# Sheet1.net
KiCad netlist of a schematic drawn in Altium Designer
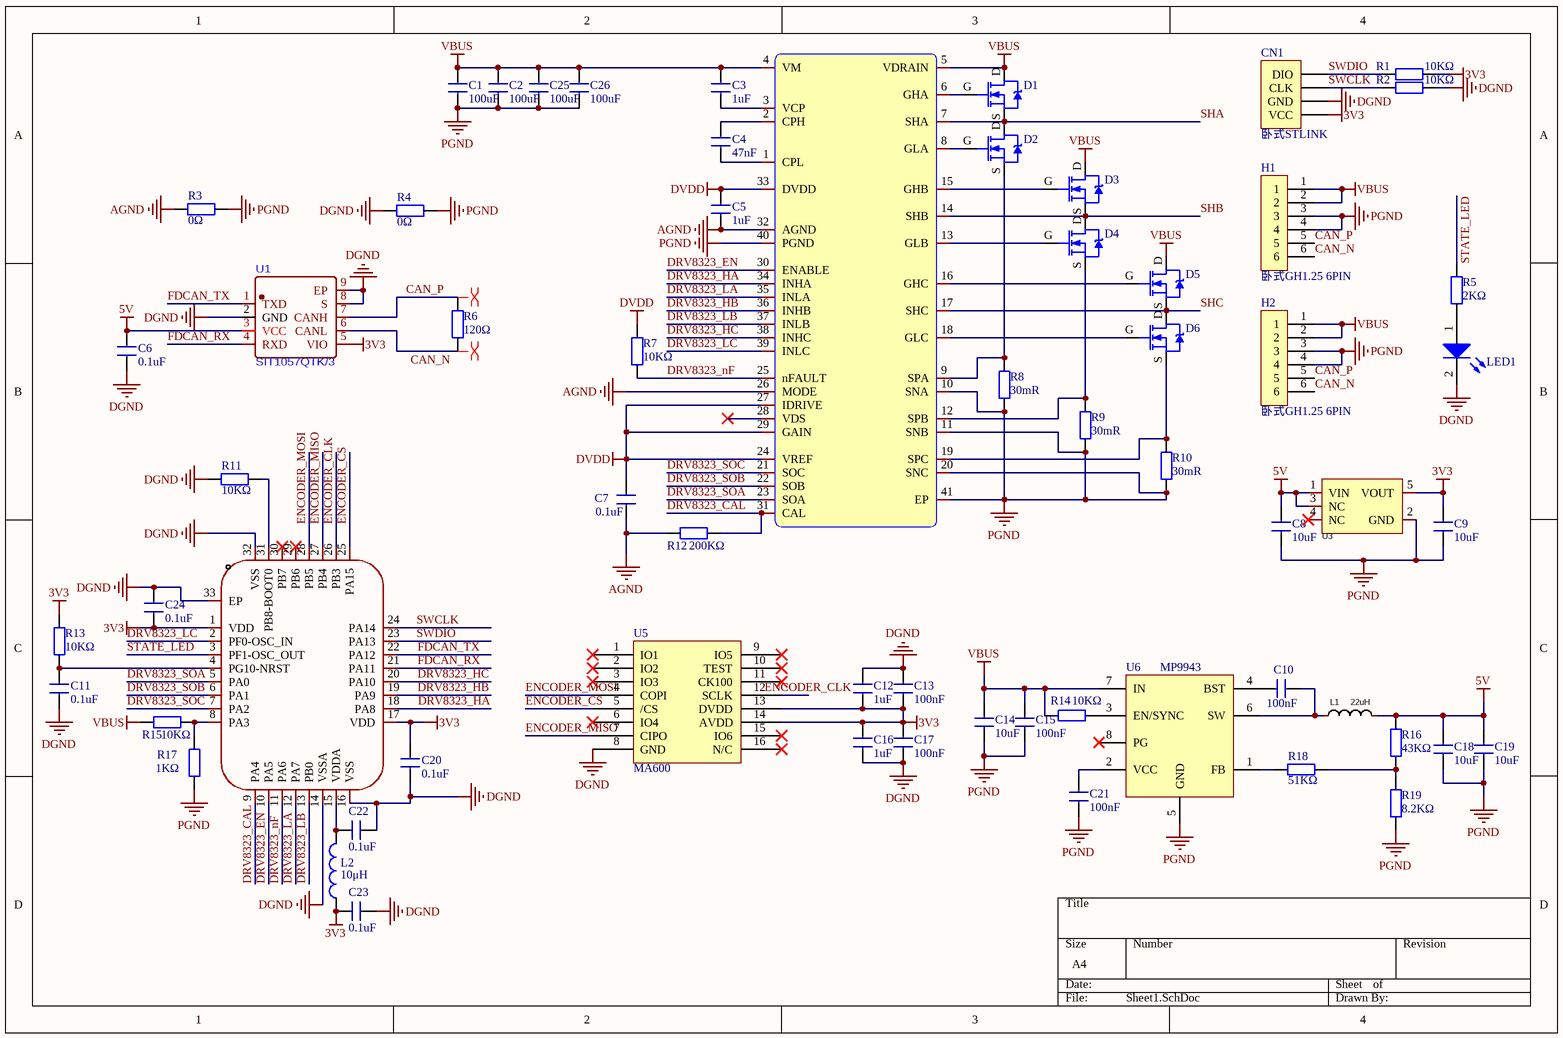
[diagram p0: Sheet1.SchDoc]

(export (version "E")
  (design (tool "Eeschema 10.0.6"))
  (components
    (comp (ref "C1")
      (value "100uF")
      (footprint "1206")
      (description "1210贴片电容")
      (libsource (lib "Integrated_Library1") (part "1210贴片电容"))
    )
    (comp (ref "C2")
      (value "100uF")
      (footprint "1206")
      (description "1210贴片电容")
      (libsource (lib "Integrated_Library1") (part "1210贴片电容"))
    )
    (comp (ref "C3")
      (value "1uF")
      (footprint "c0402")
      (description "贴片电容0402")
      (libsource (lib "Integrated_Library1") (part "0402贴片电容"))
    )
    (comp (ref "C4")
      (value "47nF")
      (footprint "c0402")
      (description "贴片电容0402")
      (libsource (lib "Integrated_Library1") (part "0402贴片电容"))
    )
    (comp (ref "C5")
      (value "1uF")
      (footprint "c0402")
      (description "贴片电容0402")
      (libsource (lib "Integrated_Library1") (part "0402贴片电容"))
    )
    (comp (ref "C6")
      (value "0.1uF")
      (footprint "c0402")
      (description "贴片电容0402")
      (libsource (lib "Integrated_Library1") (part "0402贴片电容"))
    )
    (comp (ref "C7")
      (value "0.1uF")
      (footprint "c0402")
      (description "贴片电容0402")
      (libsource (lib "Integrated_Library1") (part "0402贴片电容"))
    )
    (comp (ref "C8")
      (value "10uF")
      (footprint "c0402")
      (description "贴片电容0402")
      (libsource (lib "Integrated_Library1") (part "0402贴片电容"))
    )
    (comp (ref "C9")
      (value "10uF")
      (footprint "c0402")
      (description "贴片电容0402")
      (libsource (lib "Integrated_Library1") (part "0402贴片电容"))
    )
    (comp (ref "C10")
      (value "100nF")
      (footprint "c0402")
      (description "贴片电容0402")
      (libsource (lib "Integrated_Library1") (part "0402贴片电容"))
    )
    (comp (ref "C11")
      (value "0.1uF")
      (footprint "c0402")
      (description "贴片电容0402")
      (libsource (lib "Integrated_Library1") (part "0402贴片电容"))
    )
    (comp (ref "C12")
      (value "1uF")
      (footprint "C0402")
      (description "贴片电容0402")
      (libsource (lib "Integrated_Library1") (part "0402贴片电容"))
    )
    (comp (ref "C13")
      (value "100nF")
      (footprint "C0402")
      (description "贴片电容0402")
      (libsource (lib "Integrated_Library1") (part "0402贴片电容"))
    )
    (comp (ref "C14")
      (value "10uF")
      (footprint "C0603")
      (description "1210贴片电容")
      (libsource (lib "Integrated_Library1") (part "1210贴片电容"))
    )
    (comp (ref "C15")
      (value "100nF")
      (footprint "c0402")
      (description "贴片电容0402")
      (libsource (lib "Integrated_Library1") (part "0402贴片电容"))
    )
    (comp (ref "C16")
      (value "1uF")
      (footprint "C0402")
      (description "贴片电容0402")
      (libsource (lib "Integrated_Library1") (part "0402贴片电容"))
    )
    (comp (ref "C17")
      (value "100nF")
      (footprint "C0402")
      (description "贴片电容0402")
      (libsource (lib "Integrated_Library1") (part "0402贴片电容"))
    )
    (comp (ref "C18")
      (value "10uF")
      (footprint "C0603")
      (description "1210贴片电容")
      (libsource (lib "Integrated_Library1") (part "1210贴片电容"))
    )
    (comp (ref "C19")
      (value "10uF")
      (footprint "C0603")
      (description "1210贴片电容")
      (libsource (lib "Integrated_Library1") (part "1210贴片电容"))
    )
    (comp (ref "C20")
      (value "0.1uF")
      (footprint "c0402")
      (description "贴片电容0402")
      (libsource (lib "Integrated_Library1") (part "0402贴片电容"))
    )
    (comp (ref "C21")
      (value "100nF")
      (footprint "c0402")
      (description "贴片电容0402")
      (libsource (lib "Integrated_Library1") (part "0402贴片电容"))
    )
    (comp (ref "C22")
      (value "0.1uF")
      (footprint "c0402")
      (description "贴片电容0402")
      (libsource (lib "Integrated_Library1") (part "0402贴片电容"))
    )
    (comp (ref "C23")
      (value "0.1uF")
      (footprint "c0402")
      (description "贴片电容0402")
      (libsource (lib "Integrated_Library1") (part "0402贴片电容"))
    )
    (comp (ref "C24")
      (value "0.1uF")
      (footprint "c0402")
      (description "贴片电容0402")
      (libsource (lib "Integrated_Library1") (part "0402贴片电容"))
    )
    (comp (ref "C25")
      (value "100uF")
      (footprint "1206")
      (description "1210贴片电容")
      (libsource (lib "Integrated_Library1") (part "1210贴片电容"))
    )
    (comp (ref "C26")
      (value "100uF")
      (footprint "1206")
      (description "1210贴片电容")
      (libsource (lib "Integrated_Library1") (part "1210贴片电容"))
    )
    (comp (ref "CN1")
      (value "卧式STLINK")
      (footprint "CONN-SMD_4P-P1.25_GH1.25-4P")
      (libsource (lib "Integrated_Library1") (part "卧式STLINK"))
    )
    (comp (ref "D1")
      (value "NTMFS5C410NL")
      (footprint "DFN-8_L3.0-W3.0-P0.65-BL")
      (description "N沟道MOS管")
      (fields (field (name "PUBLISHER") "Altium Limited"))
      (libsource (lib "En") (part "NTMFS5C410NL"))
    )
    (comp (ref "D2")
      (value "NTMFS5C410NL")
      (footprint "DFN-8_L3.0-W3.0-P0.65-BL")
      (description "N沟道MOS管")
      (fields (field (name "PUBLISHER") "Altium Limited"))
      (libsource (lib "En") (part "NTMFS5C410NL"))
    )
    (comp (ref "D3")
      (value "NTMFS5C410NL")
      (footprint "DFN-8_L3.0-W3.0-P0.65-BL")
      (description "N沟道MOS管")
      (fields (field (name "PUBLISHER") "Altium Limited"))
      (libsource (lib "En") (part "NTMFS5C410NL"))
    )
    (comp (ref "D4")
      (value "NTMFS5C410NL")
      (footprint "DFN-8_L3.0-W3.0-P0.65-BL")
      (description "N沟道MOS管")
      (fields (field (name "PUBLISHER") "Altium Limited"))
      (libsource (lib "En") (part "NTMFS5C410NL"))
    )
    (comp (ref "D5")
      (value "NTMFS5C410NL")
      (footprint "DFN-8_L3.0-W3.0-P0.65-BL")
      (description "N沟道MOS管")
      (fields (field (name "PUBLISHER") "Altium Limited"))
      (libsource (lib "En") (part "NTMFS5C410NL"))
    )
    (comp (ref "D6")
      (value "NTMFS5C410NL")
      (footprint "DFN-8_L3.0-W3.0-P0.65-BL")
      (description "N沟道MOS管")
      (fields (field (name "PUBLISHER") "Altium Limited"))
      (libsource (lib "En") (part "NTMFS5C410NL"))
    )
    (comp (ref "H1")
      (value "卧式GH1.25 6PIN")
      (footprint "CONN-SMD_6P-P1.50_ZX-ZH1.5-6PWT")
      (libsource (lib "Integrated_Library1") (part "卧式GH1.25 6PIN"))
    )
    (comp (ref "H2")
      (value "卧式GH1.25 6PIN")
      (footprint "CONN-SMD_6P-P1.50_ZX-ZH1.5-6PWT")
      (libsource (lib "Integrated_Library1") (part "卧式GH1.25 6PIN"))
    )
    (comp (ref "L1")
      (value "22uH")
      (footprint "IND-SMD_L2.5-W2.0")
      (description "一体成型屏蔽电感，0530封装，额定电流3A")
      (fields (field (name "MANUFACTURER") "XR(祥如)") (field (name "MANUFACTURER PART") "XR0530-100M"))
      (libsource (lib "Integrated_Library1") (part "0530屏蔽电感"))
    )
    (comp (ref "L2")
      (value "10μH")
      (footprint "L0805")
      (description "0805贴片电感")
      (libsource (lib "Integrated_Library1") (part "0805贴片电感"))
    )
    (comp (ref "LED1")
      (value "LED")
      (footprint "led0805")
      (description "0805贴片LED")
      (libsource (lib "Integrated_Library1") (part "0805贴片LED"))
    )
    (comp (ref "R1")
      (value "10KΩ")
      (footprint "R0402")
      (description "0402贴片电阻")
      (libsource (lib "") (part "0402贴片电阻_3"))
    )
    (comp (ref "R2")
      (value "10KΩ")
      (footprint "R0402")
      (description "0402贴片电阻")
      (libsource (lib "") (part "0402贴片电阻_3"))
    )
    (comp (ref "R3")
      (value "0Ω")
      (footprint "R0402")
      (description "0402贴片电阻")
      (libsource (lib "") (part "0402贴片电阻_3"))
    )
    (comp (ref "R4")
      (value "0Ω")
      (footprint "R0402")
      (description "0402贴片电阻")
      (libsource (lib "") (part "0402贴片电阻_3"))
    )
    (comp (ref "R5")
      (value "2KΩ")
      (footprint "R0402")
      (description "0402贴片电阻")
      (libsource (lib "Integrated_Library1") (part "0402贴片电阻"))
    )
    (comp (ref "R6")
      (value "120Ω")
      (footprint "R0402")
      (description "0402贴片电阻")
      (libsource (lib "") (part "0402贴片电阻_5"))
    )
    (comp (ref "R7")
      (value "10KΩ")
      (footprint "R0402")
      (description "0402贴片电阻")
      (libsource (lib "Integrated_Library1") (part "0402贴片电阻"))
    )
    (comp (ref "R8")
      (value "30mR")
      (footprint "1206")
      (description "2512检流电阻")
      (libsource (lib "Integrated_Library1") (part "2512检流电阻"))
    )
    (comp (ref "R9")
      (value "30mR")
      (footprint "1206")
      (description "2512检流电阻")
      (libsource (lib "Integrated_Library1") (part "2512检流电阻"))
    )
    (comp (ref "R10")
      (value "30mR")
      (footprint "1206")
      (description "2512检流电阻")
      (libsource (lib "Integrated_Library1") (part "2512检流电阻"))
    )
    (comp (ref "R11")
      (value "10KΩ")
      (footprint "R0402")
      (description "0402贴片电阻")
      (libsource (lib "") (part "0402贴片电阻_3"))
    )
    (comp (ref "R12")
      (value "200KΩ")
      (footprint "R0402")
      (description "0402贴片电阻")
      (libsource (lib "") (part "0402贴片电阻_2"))
    )
    (comp (ref "R13")
      (value "10KΩ")
      (footprint "R0402")
      (description "0402贴片电阻")
      (libsource (lib "Integrated_Library1") (part "0402贴片电阻"))
    )
    (comp (ref "R14")
      (value "10KΩ")
      (footprint "R0402")
      (description "0402贴片电阻")
      (libsource (lib "") (part "0402贴片电阻_1"))
    )
    (comp (ref "R15")
      (value "10KΩ")
      (footprint "R0402")
      (description "0402贴片电阻")
      (libsource (lib "") (part "0402贴片电阻_2"))
    )
    (comp (ref "R16")
      (value "43KΩ")
      (footprint "R0402")
      (description "0402贴片电阻")
      (libsource (lib "") (part "0402贴片电阻_4"))
    )
    (comp (ref "R17")
      (value "1KΩ")
      (footprint "R0402")
      (description "0402贴片电阻")
      (libsource (lib "Integrated_Library1") (part "0402贴片电阻"))
    )
    (comp (ref "R18")
      (value "51KΩ")
      (footprint "R0402")
      (description "0402贴片电阻")
      (libsource (lib "") (part "0402贴片电阻_1"))
    )
    (comp (ref "R19")
      (value "8.2KΩ")
      (footprint "R0402")
      (description "0402贴片电阻")
      (libsource (lib "") (part "0402贴片电阻_4"))
    )
    (comp (ref "U1")
      (value "SIT1057QTK/3")
      (footprint "DFN-8_L3.0-W3.0-P0.65-BL-EP")
      (libsource (lib "En") (part "SIT1057QTK/3"))
    )
    (comp (ref "U2")
      (value "DRV8323HRTAR")
      (footprint "QFN-40_L6.0-W6.0-P0.50-BL-EP4.5")
      (fields (field (name "MANUFACTURER") "TI(德州仪器)"))
      (libsource (lib "Integrated_Library1") (part "DRV8323HRTAR"))
    )
    (comp (ref "U3")
      (value "XC6201P332MR-HXY")
      (footprint "SOT-23-5_L3.0-W1.7-P0.95-LS2.8-BR")
      (description "3.3V LDO")
      (fields (field (name "MANUFACTURER") "HXY MOSFET(华轩阳电子)"))
      (libsource (lib "Integrated_Library1") (part "XC6201P332MR-HXY"))
    )
    (comp (ref "U4")
      (value "STM32G431KBU3")
      (footprint "UFQFPN-32_L5.0-W5.0-P0.50-BL-EP3.5")
      (fields (field (name "MANUFACTURER") "ST(意法半导体)"))
      (libsource (lib "Integrated_Library1") (part "STM32G431KBU3"))
    )
    (comp (ref "U5")
      (value "MA600")
      (footprint "qfn-16-l3.0-w3.0-p0.50-tl-ep1.7")
      (description "磁编码器")
      (libsource (lib "Integrated_Library1") (part "MA600"))
    )
    (comp (ref "U6")
      (value "MP9943")
      (footprint "QFN-8 3x3")
      (libsource (lib "Integrated_Library1") (part "MP9943"))
    )
  )
  (nets
    (net (code "2") (name "/CAN_N") (class "Default")
      (node (ref "H1") (pin "6") (pinfunction "6_6") (pintype "passive"))
      (node (ref "H2") (pin "6") (pinfunction "6_6") (pintype "passive"))
      (node (ref "R6") (pin "1") (pinfunction "1_1") (pintype "passive"))
      (node (ref "U1") (pin "6") (pinfunction "CANL_6") (pintype "passive"))
    )
    (net (code "3") (name "/CAN_P") (class "Default")
      (node (ref "H1") (pin "5") (pinfunction "5_5") (pintype "passive"))
      (node (ref "H2") (pin "5") (pinfunction "5_5") (pintype "passive"))
      (node (ref "R6") (pin "2") (pinfunction "2_2") (pintype "passive"))
      (node (ref "U1") (pin "7") (pinfunction "CANH_7") (pintype "passive"))
    )
    (net (code "4") (name "/DRV8323_CAL") (class "Default")
      (node (ref "R12") (pin "1") (pinfunction "1_1") (pintype "passive"))
      (node (ref "U2") (pin "31") (pinfunction "CAL_31") (pintype "passive"))
      (node (ref "U4") (pin "9") (pinfunction "PA4_9") (pintype "passive"))
    )
    (net (code "5") (name "/DRV8323_EN") (class "Default")
      (node (ref "U2") (pin "30") (pinfunction "ENABLE_30") (pintype "passive"))
      (node (ref "U4") (pin "10") (pinfunction "PA5_10") (pintype "passive"))
    )
    (net (code "6") (name "/DRV8323_HA") (class "Default")
      (node (ref "U2") (pin "34") (pinfunction "INHA_34") (pintype "passive"))
      (node (ref "U4") (pin "18") (pinfunction "PA8_18") (pintype "passive"))
    )
    (net (code "7") (name "/DRV8323_HB") (class "Default")
      (node (ref "U2") (pin "36") (pinfunction "INHB_36") (pintype "passive"))
      (node (ref "U4") (pin "19") (pinfunction "PA9_19") (pintype "passive"))
    )
    (net (code "8") (name "/DRV8323_HC") (class "Default")
      (node (ref "U2") (pin "38") (pinfunction "INHC_38") (pintype "passive"))
      (node (ref "U4") (pin "20") (pinfunction "PA10_20") (pintype "passive"))
    )
    (net (code "9") (name "/DRV8323_LA") (class "Default")
      (node (ref "U2") (pin "35") (pinfunction "INLA_35") (pintype "passive"))
      (node (ref "U4") (pin "12") (pinfunction "PA7_12") (pintype "passive"))
    )
    (net (code "10") (name "/DRV8323_LB") (class "Default")
      (node (ref "U2") (pin "37") (pinfunction "INLB_37") (pintype "passive"))
      (node (ref "U4") (pin "13") (pinfunction "PB0_13") (pintype "passive"))
    )
    (net (code "11") (name "/DRV8323_LC") (class "Default")
      (node (ref "U2") (pin "39") (pinfunction "INLC_39") (pintype "passive"))
      (node (ref "U4") (pin "2") (pinfunction "PF0-OSC_IN_2") (pintype "passive"))
    )
    (net (code "12") (name "/DRV8323_SOA") (class "Default")
      (node (ref "U2") (pin "23") (pinfunction "SOA_23") (pintype "passive"))
      (node (ref "U4") (pin "5") (pinfunction "PA0_5") (pintype "passive"))
    )
    (net (code "13") (name "/DRV8323_SOB") (class "Default")
      (node (ref "U2") (pin "22") (pinfunction "SOB_22") (pintype "passive"))
      (node (ref "U4") (pin "6") (pinfunction "PA1_6") (pintype "passive"))
    )
    (net (code "14") (name "/DRV8323_SOC") (class "Default")
      (node (ref "U2") (pin "21") (pinfunction "SOC_21") (pintype "passive"))
      (node (ref "U4") (pin "7") (pinfunction "PA2_7") (pintype "passive"))
    )
    (net (code "15") (name "/DRV8323_nF") (class "Default")
      (node (ref "R7") (pin "2") (pinfunction "2_2") (pintype "passive"))
      (node (ref "U2") (pin "25") (pinfunction "nFAULT_25") (pintype "passive"))
      (node (ref "U4") (pin "11") (pinfunction "PA6_11") (pintype "passive"))
    )
    (net (code "16") (name "/ENCODER_CLK") (class "Default")
      (node (ref "U4") (pin "26") (pinfunction "PB3_26") (pintype "passive"))
      (node (ref "U5") (pin "12") (pinfunction "SCLK_12") (pintype "passive"))
    )
    (net (code "17") (name "/ENCODER_CS") (class "Default")
      (node (ref "U4") (pin "25") (pinfunction "PA15_25") (pintype "passive"))
      (node (ref "U5") (pin "5") (pinfunction "/CS_5") (pintype "passive"))
    )
    (net (code "18") (name "/ENCODER_MISO") (class "Default")
      (node (ref "U4") (pin "27") (pinfunction "PB4_27") (pintype "passive"))
      (node (ref "U5") (pin "7") (pinfunction "CIPO_7") (pintype "passive"))
    )
    (net (code "19") (name "/ENCODER_MOSI") (class "Default")
      (node (ref "U4") (pin "28") (pinfunction "PB5_28") (pintype "passive"))
      (node (ref "U5") (pin "4") (pinfunction "COPI_4") (pintype "passive"))
    )
    (net (code "20") (name "/FDCAN_RX") (class "Default")
      (node (ref "U1") (pin "4") (pinfunction "RXD_4") (pintype "passive"))
      (node (ref "U4") (pin "21") (pinfunction "PA11_21") (pintype "passive"))
    )
    (net (code "21") (name "/FDCAN_TX") (class "Default")
      (node (ref "U1") (pin "1") (pinfunction "TXD_1") (pintype "passive"))
      (node (ref "U4") (pin "22") (pinfunction "PA12_22") (pintype "passive"))
    )
    (net (code "22") (name "/SHA") (class "Default")
      (node (ref "D1") (pin "S") (pinfunction "S_S") (pintype "passive"))
      (node (ref "D2") (pin "D") (pinfunction "D_D") (pintype "passive"))
      (node (ref "U2") (pin "7") (pinfunction "SHA_7") (pintype "passive"))
    )
    (net (code "23") (name "/SHB") (class "Default")
      (node (ref "D3") (pin "S") (pinfunction "S_S") (pintype "passive"))
      (node (ref "D4") (pin "D") (pinfunction "D_D") (pintype "passive"))
      (node (ref "U2") (pin "14") (pinfunction "SHB_14") (pintype "passive"))
    )
    (net (code "24") (name "/SHC") (class "Default")
      (node (ref "D5") (pin "S") (pinfunction "S_S") (pintype "passive"))
      (node (ref "D6") (pin "D") (pinfunction "D_D") (pintype "passive"))
      (node (ref "U2") (pin "17") (pinfunction "SHC_17") (pintype "passive"))
    )
    (net (code "25") (name "/STATE_LED") (class "Default")
      (node (ref "R5") (pin "1") (pinfunction "1_1") (pintype "passive"))
      (node (ref "U4") (pin "3") (pinfunction "PF1-OSC_OUT_3") (pintype "passive"))
    )
    (net (code "26") (name "/SWCLK") (class "Default")
      (node (ref "CN1") (pin "3") (pinfunction "CLK_3") (pintype "passive"))
      (node (ref "R2") (pin "1") (pinfunction "1_1") (pintype "passive"))
      (node (ref "U4") (pin "24") (pinfunction "PA14_24") (pintype "passive"))
    )
    (net (code "27") (name "/SWDIO") (class "Default")
      (node (ref "CN1") (pin "4") (pinfunction "DIO_4") (pintype "passive"))
      (node (ref "R1") (pin "1") (pinfunction "1_1") (pintype "passive"))
      (node (ref "U4") (pin "23") (pinfunction "PA13_23") (pintype "passive"))
    )
    (net (code "28") (name "3V3") (class "Default")
      (node (ref "C12") (pin "1") (pinfunction "1_1") (pintype "passive"))
      (node (ref "C13") (pin "1") (pinfunction "1_1") (pintype "passive"))
      (node (ref "C16") (pin "2") (pinfunction "2_2") (pintype "passive"))
      (node (ref "C17") (pin "2") (pinfunction "2_2") (pintype "passive"))
      (node (ref "C20") (pin "1") (pinfunction "1_1") (pintype "passive"))
      (node (ref "C23") (pin "2") (pinfunction "2_2") (pintype "passive"))
      (node (ref "C24") (pin "1") (pinfunction "1_1") (pintype "passive"))
      (node (ref "C9") (pin "2") (pinfunction "2_2") (pintype "passive"))
      (node (ref "CN1") (pin "1") (pinfunction "VCC_1") (pintype "passive"))
      (node (ref "L2") (pin "1") (pinfunction "1_1") (pintype "passive"))
      (node (ref "R1") (pin "2") (pinfunction "2_2") (pintype "passive"))
      (node (ref "R13") (pin "1") (pinfunction "1_1") (pintype "passive"))
      (node (ref "U1") (pin "5") (pinfunction "VIO_5") (pintype "passive"))
      (node (ref "U3") (pin "5") (pinfunction "VOUT_5") (pintype "passive"))
      (node (ref "U4") (pin "1") (pinfunction "VDD_1") (pintype "passive"))
      (node (ref "U4") (pin "17") (pinfunction "VDD_17") (pintype "passive"))
      (node (ref "U5") (pin "13") (pinfunction "DVDD_13") (pintype "passive"))
      (node (ref "U5") (pin "14") (pinfunction "AVDD_14") (pintype "passive"))
    )
    (net (code "29") (name "5V") (class "Default")
      (node (ref "C18") (pin "2") (pinfunction "2_2") (pintype "passive"))
      (node (ref "C19") (pin "2") (pinfunction "2_2") (pintype "passive"))
      (node (ref "C6") (pin "2") (pinfunction "2_2") (pintype "passive"))
      (node (ref "C8") (pin "2") (pinfunction "2_2") (pintype "passive"))
      (node (ref "L1") (pin "2") (pinfunction "2_2") (pintype "passive"))
      (node (ref "R16") (pin "2") (pinfunction "2_2") (pintype "passive"))
      (node (ref "U1") (pin "3") (pinfunction "VCC_3") (pintype "passive"))
      (node (ref "U3") (pin "1") (pinfunction "VIN_1") (pintype "passive"))
      (node (ref "U3") (pin "3") (pinfunction "NC_3") (pintype "passive"))
    )
    (net (code "30") (name "AGND") (class "Default")
      (node (ref "C5") (pin "1") (pinfunction "1_1") (pintype "passive"))
      (node (ref "C7") (pin "1") (pinfunction "1_1") (pintype "passive"))
      (node (ref "R12") (pin "2") (pinfunction "2_2") (pintype "passive"))
      (node (ref "R3") (pin "1") (pinfunction "1_1") (pintype "passive"))
      (node (ref "U2") (pin "26") (pinfunction "MODE_26") (pintype "passive"))
      (node (ref "U2") (pin "32") (pinfunction "AGND_32") (pintype "passive"))
    )
    (net (code "31") (name "DGND") (class "Default")
      (node (ref "C11") (pin "1") (pinfunction "1_1") (pintype "passive"))
      (node (ref "C12") (pin "2") (pinfunction "2_2") (pintype "passive"))
      (node (ref "C13") (pin "2") (pinfunction "2_2") (pintype "passive"))
      (node (ref "C16") (pin "1") (pinfunction "1_1") (pintype "passive"))
      (node (ref "C17") (pin "1") (pinfunction "1_1") (pintype "passive"))
      (node (ref "C20") (pin "2") (pinfunction "2_2") (pintype "passive"))
      (node (ref "C22") (pin "1") (pinfunction "1_1") (pintype "passive"))
      (node (ref "C23") (pin "1") (pinfunction "1_1") (pintype "passive"))
      (node (ref "C24") (pin "2") (pinfunction "2_2") (pintype "passive"))
      (node (ref "C6") (pin "1") (pinfunction "1_1") (pintype "passive"))
      (node (ref "CN1") (pin "2") (pinfunction "GND_2") (pintype "passive"))
      (node (ref "LED1") (pin "2") (pinfunction "K_2") (pintype "passive"))
      (node (ref "R11") (pin "1") (pinfunction "1_1") (pintype "passive"))
      (node (ref "R2") (pin "2") (pinfunction "2_2") (pintype "passive"))
      (node (ref "R4") (pin "1") (pinfunction "1_1") (pintype "passive"))
      (node (ref "U1") (pin "2") (pinfunction "GND_2") (pintype "passive"))
      (node (ref "U1") (pin "8") (pinfunction "S_8") (pintype "passive"))
      (node (ref "U1") (pin "9") (pinfunction "EP_9") (pintype "passive"))
      (node (ref "U4") (pin "14") (pinfunction "VSSA_14") (pintype "passive"))
      (node (ref "U4") (pin "16") (pinfunction "VSS_16") (pintype "passive"))
      (node (ref "U4") (pin "32") (pinfunction "VSS_32") (pintype "passive"))
      (node (ref "U4") (pin "33") (pinfunction "EP_33") (pintype "passive"))
      (node (ref "U5") (pin "8") (pinfunction "GND_8") (pintype "passive"))
    )
    (net (code "32") (name "DVDD") (class "Default")
      (node (ref "C5") (pin "2") (pinfunction "2_2") (pintype "passive"))
      (node (ref "C7") (pin "2") (pinfunction "2_2") (pintype "passive"))
      (node (ref "R7") (pin "1") (pinfunction "1_1") (pintype "passive"))
      (node (ref "U2") (pin "24") (pinfunction "VREF_24") (pintype "passive"))
      (node (ref "U2") (pin "27") (pinfunction "IDRIVE_27") (pintype "passive"))
      (node (ref "U2") (pin "29") (pinfunction "GAIN_29") (pintype "passive"))
      (node (ref "U2") (pin "33") (pinfunction "DVDD_33") (pintype "passive"))
    )
    (net (code "33") (name "Net-(LED1-A)") (class "Default")
      (node (ref "LED1") (pin "1") (pinfunction "A_1") (pintype "passive"))
      (node (ref "R5") (pin "2") (pinfunction "2_2") (pintype "passive"))
    )
    (net (code "34") (name "Net-(R16-Pad1)") (class "Default")
      (node (ref "R16") (pin "1") (pinfunction "1_1") (pintype "passive"))
      (node (ref "R18") (pin "2") (pinfunction "2_2") (pintype "passive"))
      (node (ref "R19") (pin "2") (pinfunction "2_2") (pintype "passive"))
    )
    (net (code "35") (name "Net-(U2-CPH)") (class "Default")
      (node (ref "C4") (pin "2") (pinfunction "2_2") (pintype "passive"))
      (node (ref "U2") (pin "2") (pinfunction "CPH_2") (pintype "passive"))
    )
    (net (code "36") (name "Net-(U2-CPL)") (class "Default")
      (node (ref "C4") (pin "1") (pinfunction "1_1") (pintype "passive"))
      (node (ref "U2") (pin "1") (pinfunction "CPL_1") (pintype "passive"))
    )
    (net (code "37") (name "Net-(U2-GHA)") (class "Default")
      (node (ref "D1") (pin "G") (pinfunction "G_G") (pintype "passive"))
      (node (ref "U2") (pin "6") (pinfunction "GHA_6") (pintype "passive"))
    )
    (net (code "38") (name "Net-(U2-GHB)") (class "Default")
      (node (ref "D3") (pin "G") (pinfunction "G_G") (pintype "passive"))
      (node (ref "U2") (pin "15") (pinfunction "GHB_15") (pintype "passive"))
    )
    (net (code "39") (name "Net-(U2-GHC)") (class "Default")
      (node (ref "D5") (pin "G") (pinfunction "G_G") (pintype "passive"))
      (node (ref "U2") (pin "16") (pinfunction "GHC_16") (pintype "passive"))
    )
    (net (code "40") (name "Net-(U2-GLA)") (class "Default")
      (node (ref "D2") (pin "G") (pinfunction "G_G") (pintype "passive"))
      (node (ref "U2") (pin "8") (pinfunction "GLA_8") (pintype "passive"))
    )
    (net (code "41") (name "Net-(U2-GLB)") (class "Default")
      (node (ref "D4") (pin "G") (pinfunction "G_G") (pintype "passive"))
      (node (ref "U2") (pin "13") (pinfunction "GLB_13") (pintype "passive"))
    )
    (net (code "42") (name "Net-(U2-GLC)") (class "Default")
      (node (ref "D6") (pin "G") (pinfunction "G_G") (pintype "passive"))
      (node (ref "U2") (pin "18") (pinfunction "GLC_18") (pintype "passive"))
    )
    (net (code "43") (name "Net-(U2-SPA)") (class "Default")
      (node (ref "D2") (pin "S") (pinfunction "S_S") (pintype "passive"))
      (node (ref "R8") (pin "2") (pinfunction "2_2") (pintype "passive"))
      (node (ref "U2") (pin "9") (pinfunction "SPA_9") (pintype "passive"))
    )
    (net (code "44") (name "Net-(U2-SPB)") (class "Default")
      (node (ref "D4") (pin "S") (pinfunction "S_S") (pintype "passive"))
      (node (ref "R9") (pin "2") (pinfunction "2_2") (pintype "passive"))
      (node (ref "U2") (pin "12") (pinfunction "SPB_12") (pintype "passive"))
    )
    (net (code "45") (name "Net-(U2-SPC)") (class "Default")
      (node (ref "D6") (pin "S") (pinfunction "S_S") (pintype "passive"))
      (node (ref "R10") (pin "2") (pinfunction "2_2") (pintype "passive"))
      (node (ref "U2") (pin "19") (pinfunction "SPC_19") (pintype "passive"))
    )
    (net (code "46") (name "Net-(U2-VCP)") (class "Default")
      (node (ref "C3") (pin "1") (pinfunction "1_1") (pintype "passive"))
      (node (ref "U2") (pin "3") (pinfunction "VCP_3") (pintype "passive"))
    )
    (net (code "47") (name "Net-(U4-PA3)") (class "Default")
      (node (ref "R15") (pin "1") (pinfunction "1_1") (pintype "passive"))
      (node (ref "R17") (pin "1") (pinfunction "1_1") (pintype "passive"))
      (node (ref "U4") (pin "8") (pinfunction "PA3_8") (pintype "passive"))
    )
    (net (code "48") (name "Net-(U4-PB8-BOOT0)") (class "Default")
      (node (ref "R11") (pin "2") (pinfunction "2_2") (pintype "passive"))
      (node (ref "U4") (pin "31") (pinfunction "PB8-BOOT0_31") (pintype "passive"))
    )
    (net (code "49") (name "Net-(U4-PG10-NRST)") (class "Default")
      (node (ref "C11") (pin "2") (pinfunction "2_2") (pintype "passive"))
      (node (ref "R13") (pin "2") (pinfunction "2_2") (pintype "passive"))
      (node (ref "U4") (pin "4") (pinfunction "PG10-NRST_4") (pintype "passive"))
    )
    (net (code "50") (name "Net-(U4-VDDA)") (class "Default")
      (node (ref "C22") (pin "2") (pinfunction "2_2") (pintype "passive"))
      (node (ref "L2") (pin "2") (pinfunction "2_2") (pintype "passive"))
      (node (ref "U4") (pin "15") (pinfunction "VDDA_15") (pintype "passive"))
    )
    (net (code "51") (name "Net-(U6-BST)") (class "Default")
      (node (ref "C10") (pin "1") (pinfunction "1_1") (pintype "passive"))
      (node (ref "U6") (pin "4") (pinfunction "BST_4") (pintype "passive"))
    )
    (net (code "52") (name "Net-(U6-EN{slash}SYNC)") (class "Default")
      (node (ref "R14") (pin "2") (pinfunction "2_2") (pintype "passive"))
      (node (ref "U6") (pin "3") (pinfunction "EN/SYNC_3") (pintype "passive"))
    )
    (net (code "53") (name "Net-(U6-FB)") (class "Default")
      (node (ref "R18") (pin "1") (pinfunction "1_1") (pintype "passive"))
      (node (ref "U6") (pin "1") (pinfunction "FB_1") (pintype "passive"))
    )
    (net (code "54") (name "Net-(U6-SW)") (class "Default")
      (node (ref "C10") (pin "2") (pinfunction "2_2") (pintype "passive"))
      (node (ref "L1") (pin "1") (pinfunction "1_1") (pintype "passive"))
      (node (ref "U6") (pin "6") (pinfunction "SW_6") (pintype "passive"))
    )
    (net (code "55") (name "Net-(U6-VCC)") (class "Default")
      (node (ref "C21") (pin "2") (pinfunction "2_2") (pintype "passive"))
      (node (ref "U6") (pin "2") (pinfunction "VCC_2") (pintype "passive"))
    )
    (net (code "56") (name "PGND") (class "Default")
      (node (ref "C1") (pin "1") (pinfunction "1_1") (pintype "passive"))
      (node (ref "C14") (pin "1") (pinfunction "1_1") (pintype "passive"))
      (node (ref "C15") (pin "1") (pinfunction "1_1") (pintype "passive"))
      (node (ref "C18") (pin "1") (pinfunction "1_1") (pintype "passive"))
      (node (ref "C19") (pin "1") (pinfunction "1_1") (pintype "passive"))
      (node (ref "C2") (pin "1") (pinfunction "1_1") (pintype "passive"))
      (node (ref "C21") (pin "1") (pinfunction "1_1") (pintype "passive"))
      (node (ref "C25") (pin "1") (pinfunction "1_1") (pintype "passive"))
      (node (ref "C26") (pin "1") (pinfunction "1_1") (pintype "passive"))
      (node (ref "C8") (pin "1") (pinfunction "1_1") (pintype "passive"))
      (node (ref "C9") (pin "1") (pinfunction "1_1") (pintype "passive"))
      (node (ref "H1") (pin "3") (pinfunction "3_3") (pintype "passive"))
      (node (ref "H1") (pin "4") (pinfunction "4_4") (pintype "passive"))
      (node (ref "H2") (pin "3") (pinfunction "3_3") (pintype "passive"))
      (node (ref "H2") (pin "4") (pinfunction "4_4") (pintype "passive"))
      (node (ref "R10") (pin "1") (pinfunction "1_1") (pintype "passive"))
      (node (ref "R17") (pin "2") (pinfunction "2_2") (pintype "passive"))
      (node (ref "R19") (pin "1") (pinfunction "1_1") (pintype "passive"))
      (node (ref "R3") (pin "2") (pinfunction "2_2") (pintype "passive"))
      (node (ref "R4") (pin "2") (pinfunction "2_2") (pintype "passive"))
      (node (ref "R8") (pin "1") (pinfunction "1_1") (pintype "passive"))
      (node (ref "R9") (pin "1") (pinfunction "1_1") (pintype "passive"))
      (node (ref "U2") (pin "10") (pinfunction "SNA_10") (pintype "passive"))
      (node (ref "U2") (pin "11") (pinfunction "SNB_11") (pintype "passive"))
      (node (ref "U2") (pin "20") (pinfunction "SNC_20") (pintype "passive"))
      (node (ref "U2") (pin "40") (pinfunction "PGND_40") (pintype "passive"))
      (node (ref "U2") (pin "41") (pinfunction "EP_41") (pintype "passive"))
      (node (ref "U3") (pin "2") (pinfunction "GND_2") (pintype "passive"))
      (node (ref "U6") (pin "5") (pinfunction "GND_5") (pintype "passive"))
    )
    (net (code "57") (name "VBUS") (class "Default")
      (node (ref "C1") (pin "2") (pinfunction "2_2") (pintype "passive"))
      (node (ref "C14") (pin "2") (pinfunction "2_2") (pintype "passive"))
      (node (ref "C15") (pin "2") (pinfunction "2_2") (pintype "passive"))
      (node (ref "C2") (pin "2") (pinfunction "2_2") (pintype "passive"))
      (node (ref "C25") (pin "2") (pinfunction "2_2") (pintype "passive"))
      (node (ref "C26") (pin "2") (pinfunction "2_2") (pintype "passive"))
      (node (ref "C3") (pin "2") (pinfunction "2_2") (pintype "passive"))
      (node (ref "D1") (pin "D") (pinfunction "D_D") (pintype "passive"))
      (node (ref "D3") (pin "D") (pinfunction "D_D") (pintype "passive"))
      (node (ref "D5") (pin "D") (pinfunction "D_D") (pintype "passive"))
      (node (ref "H1") (pin "1") (pinfunction "1_1") (pintype "passive"))
      (node (ref "H1") (pin "2") (pinfunction "2_2") (pintype "passive"))
      (node (ref "H2") (pin "1") (pinfunction "1_1") (pintype "passive"))
      (node (ref "H2") (pin "2") (pinfunction "2_2") (pintype "passive"))
      (node (ref "R14") (pin "1") (pinfunction "1_1") (pintype "passive"))
      (node (ref "R15") (pin "2") (pinfunction "2_2") (pintype "passive"))
      (node (ref "U2") (pin "4") (pinfunction "VM_4") (pintype "passive"))
      (node (ref "U2") (pin "5") (pinfunction "VDRAIN_5") (pintype "passive"))
      (node (ref "U6") (pin "7") (pinfunction "IN_7") (pintype "passive"))
    )
    (net (code "58") (name "unconnected-(U2-VDS-Pad28)") (class "Default")
      (node (ref "U2") (pin "28") (pinfunction "VDS_28") (pintype "passive+no_connect"))
    )
    (net (code "59") (name "unconnected-(U3-NC-Pad4)") (class "Default")
      (node (ref "U3") (pin "4") (pinfunction "NC_4") (pintype "passive+no_connect"))
    )
    (net (code "60") (name "unconnected-(U4-PB6-Pad29)") (class "Default")
      (node (ref "U4") (pin "29") (pinfunction "PB6_29") (pintype "passive+no_connect"))
    )
    (net (code "61") (name "unconnected-(U4-PB7-Pad30)") (class "Default")
      (node (ref "U4") (pin "30") (pinfunction "PB7_30") (pintype "passive+no_connect"))
    )
    (net (code "62") (name "unconnected-(U5-CK100-Pad11)") (class "Default")
      (node (ref "U5") (pin "11") (pinfunction "CK100_11") (pintype "passive+no_connect"))
    )
    (net (code "63") (name "unconnected-(U5-IO1-Pad1)") (class "Default")
      (node (ref "U5") (pin "1") (pinfunction "IO1_1") (pintype "passive+no_connect"))
    )
    (net (code "64") (name "unconnected-(U5-IO2-Pad2)") (class "Default")
      (node (ref "U5") (pin "2") (pinfunction "IO2_2") (pintype "passive+no_connect"))
    )
    (net (code "65") (name "unconnected-(U5-IO3-Pad3)") (class "Default")
      (node (ref "U5") (pin "3") (pinfunction "IO3_3") (pintype "passive+no_connect"))
    )
    (net (code "66") (name "unconnected-(U5-IO4-Pad6)") (class "Default")
      (node (ref "U5") (pin "6") (pinfunction "IO4_6") (pintype "passive+no_connect"))
    )
    (net (code "67") (name "unconnected-(U5-IO5-Pad9)") (class "Default")
      (node (ref "U5") (pin "9") (pinfunction "IO5_9") (pintype "passive+no_connect"))
    )
    (net (code "68") (name "unconnected-(U5-IO6-Pad15)") (class "Default")
      (node (ref "U5") (pin "15") (pinfunction "IO6_15") (pintype "passive+no_connect"))
    )
    (net (code "69") (name "unconnected-(U5-N{slash}C-Pad16)") (class "Default")
      (node (ref "U5") (pin "16") (pinfunction "N/C_16") (pintype "passive+no_connect"))
    )
    (net (code "70") (name "unconnected-(U5-TEST-Pad10)") (class "Default")
      (node (ref "U5") (pin "10") (pinfunction "TEST_10") (pintype "passive+no_connect"))
    )
    (net (code "71") (name "unconnected-(U6-PG-Pad8)") (class "Default")
      (node (ref "U6") (pin "8") (pinfunction "PG_8") (pintype "passive+no_connect"))
    )
  )
)
